# Schem_WS_v2.net
KiCad netlist of a schematic drawn in Altium Designer
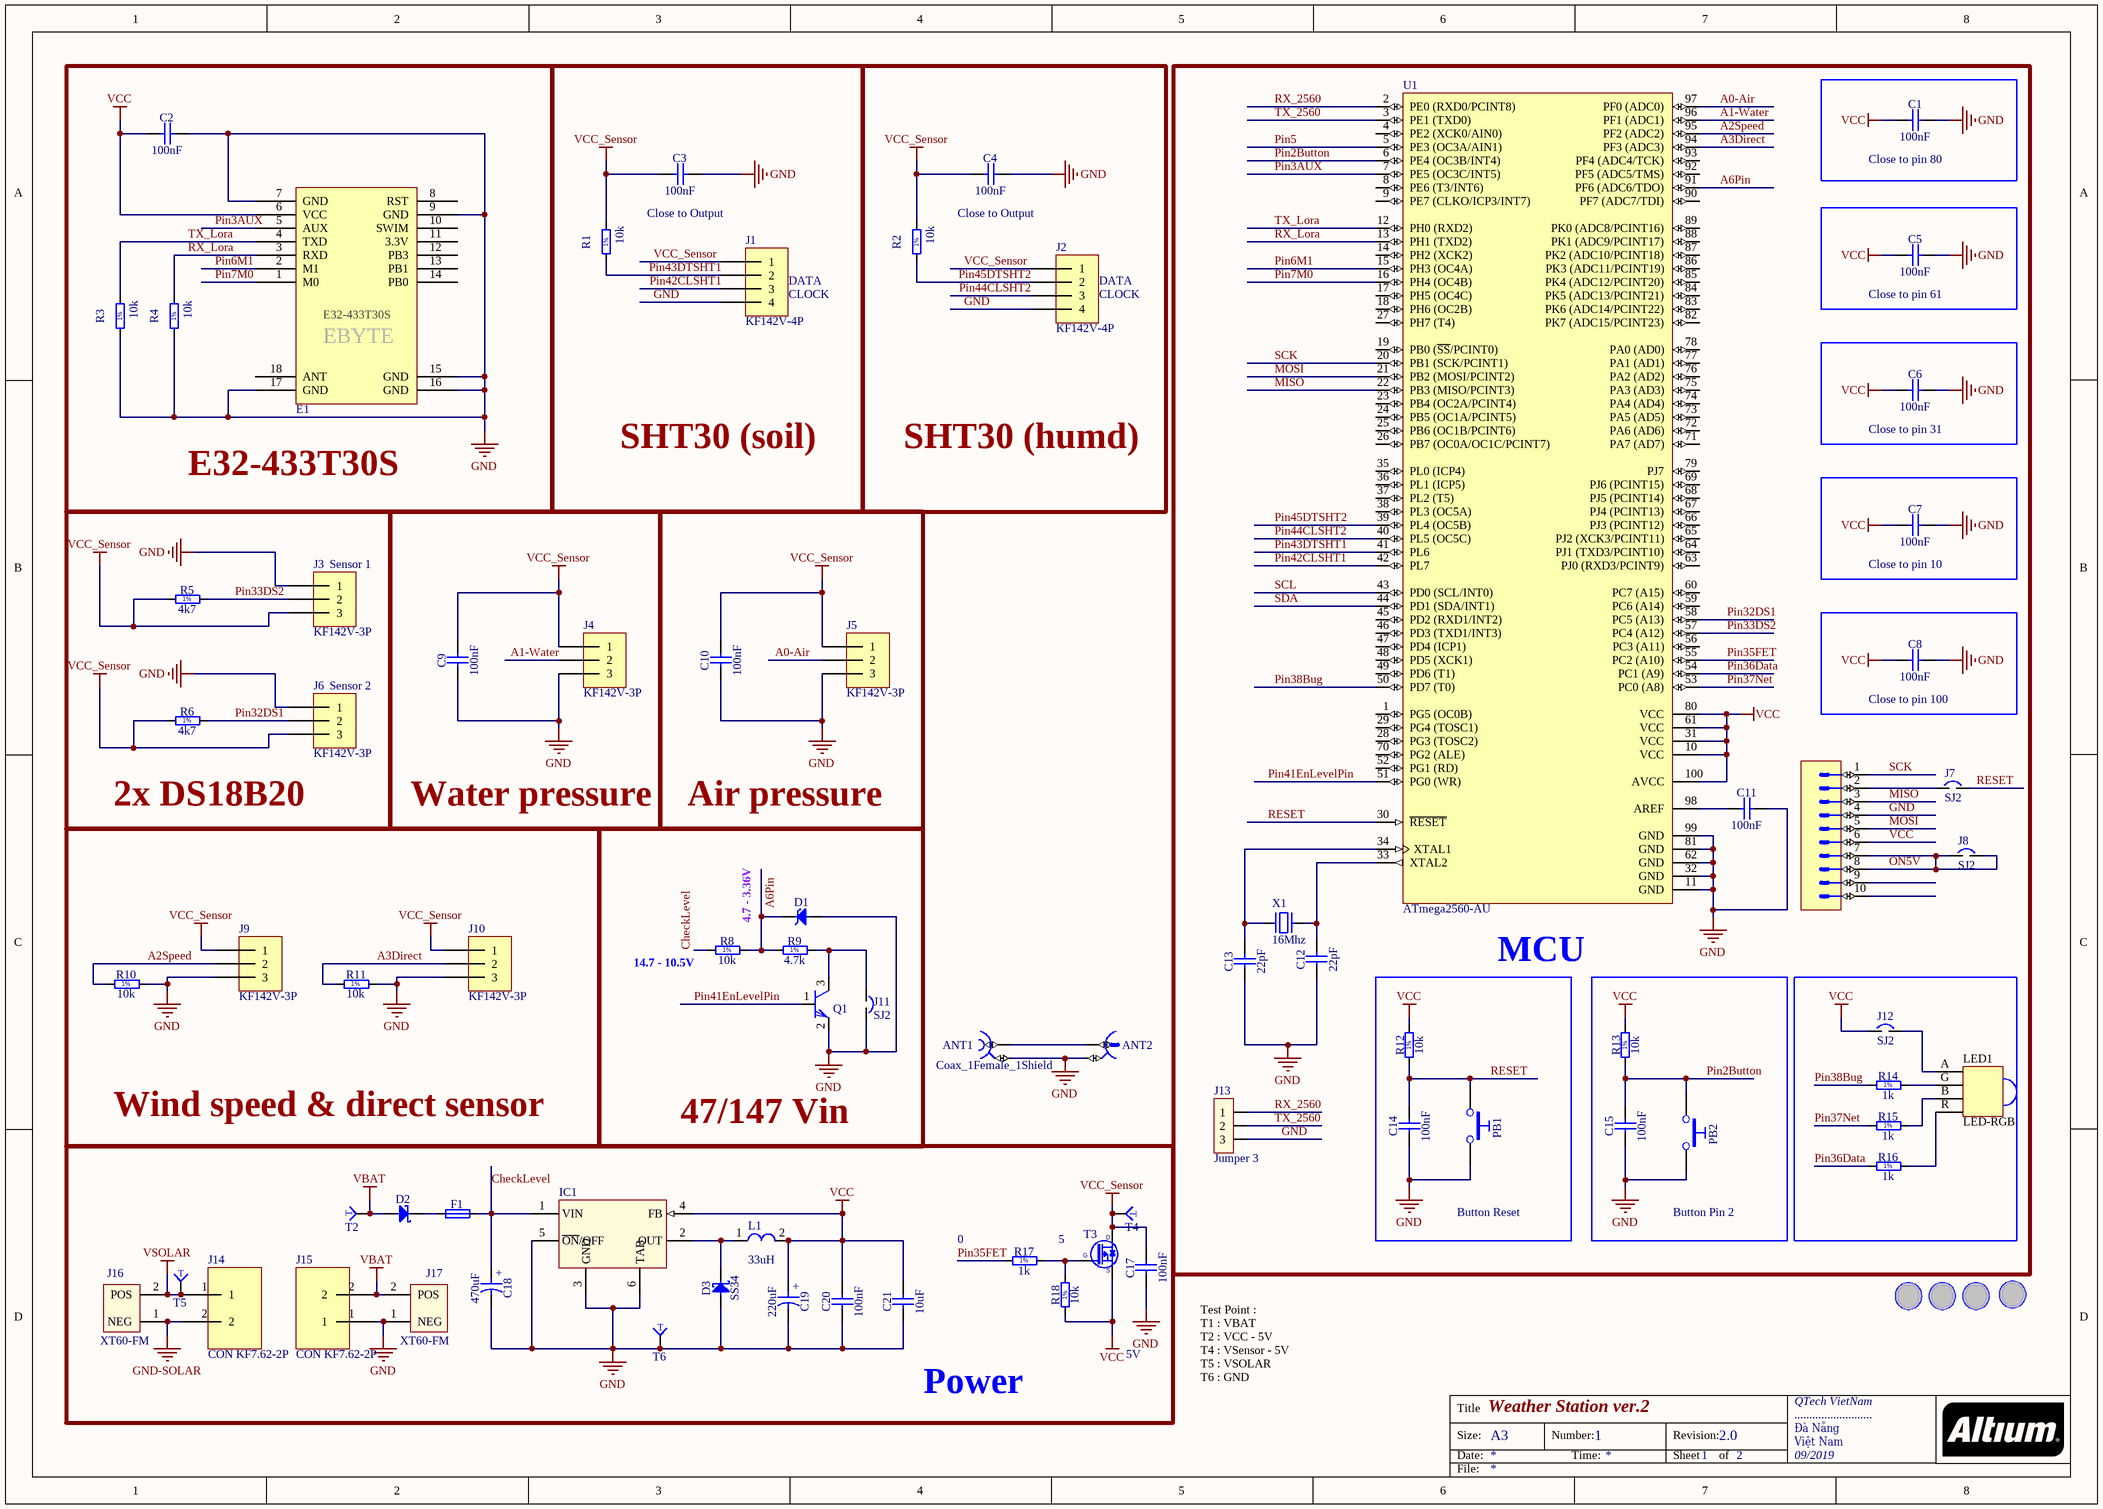
[diagram p0: Schem_WS_v2.SchDoc]

(export (version "E")
  (design (tool "Eeschema 10.0.6"))
  (components
    (comp (ref "ANT1")
      (value "Coax_1Female_1Shield")
      (footprint "HUBER-SUHNER_85 SMA-50-0-101/111 NE")
      (fields
        (field (name "PART NUMBER") "HUBER-SUHNER_85_SMA-50-0-101/111_NE")
        (field (name "MANUFACTURER") "HUBER+SUHNER")
        (field (name "MANUFACTURER PART NUMBER") "85_SMA-50-0-101/111_NE")
        (field (name "AUTHOR") "CERN DEM JLC")
      )
      (libsource (lib "Connectors") (part "Coax_1Female_1Shield"))
    )
    (comp (ref "ANT2")
      (value "U.FL")
      (footprint "HIROSE_U.FL-R-SMT-1(10)")
      (fields
        (field (name "PART NUMBER") "HIROSE_U.FL-R-SMT-1(10)")
        (field (name "MANUFACTURER") "HIROSE (HRS)")
        (field (name "MANUFACTURER PART NUMBER") "U.FL-R-SMT-1(10)")
        (field (name "AUTHOR") "CERN DEM JLC")
      )
      (libsource (lib "Connectors") (part "Coax_1Male_1Shield"))
    )
    (comp (ref "C1")
      (value "100nF")
      (footprint "CAPC1608X87N")
      (description "Non-polarised capacitor")
      (fields
        (field (name "PART NUMBER") "CC0603_100NF_50V_10%_X7R")
        (field (name "VOLTAGE") "50V")
        (field (name "AUTHOR") "CERN DEM JLC")
      )
      (libsource (lib "Capacitors") (part "Capacitor - non polarized"))
    )
    (comp (ref "C2")
      (value "100nF")
      (footprint "CAPC1608X87N")
      (description "Non-polarised capacitor")
      (fields
        (field (name "PART NUMBER") "CC0603_100NF_50V_10%_X7R")
        (field (name "VOLTAGE") "50V")
        (field (name "AUTHOR") "CERN DEM JLC")
      )
      (libsource (lib "Capacitors") (part "Capacitor - non polarized"))
    )
    (comp (ref "C3")
      (value "100nF")
      (footprint "CAPC1608X87N")
      (description "Non-polarised capacitor")
      (fields
        (field (name "PART NUMBER") "CC0603_100NF_50V_10%_X7R")
        (field (name "VOLTAGE") "50V")
        (field (name "AUTHOR") "CERN DEM JLC")
      )
      (libsource (lib "Capacitors") (part "Capacitor - non polarized"))
    )
    (comp (ref "C4")
      (value "100nF")
      (footprint "CAPC1608X87N")
      (description "Non-polarised capacitor")
      (fields
        (field (name "PART NUMBER") "CC0603_100NF_50V_10%_X7R")
        (field (name "VOLTAGE") "50V")
        (field (name "AUTHOR") "CERN DEM JLC")
      )
      (libsource (lib "Capacitors") (part "Capacitor - non polarized"))
    )
    (comp (ref "C5")
      (value "100nF")
      (footprint "CAPC1608X87N")
      (description "Non-polarised capacitor")
      (fields
        (field (name "PART NUMBER") "CC0603_100NF_50V_10%_X7R")
        (field (name "VOLTAGE") "50V")
        (field (name "AUTHOR") "CERN DEM JLC")
      )
      (libsource (lib "Capacitors") (part "Capacitor - non polarized"))
    )
    (comp (ref "C6")
      (value "100nF")
      (footprint "CAPC1608X87N")
      (description "Non-polarised capacitor")
      (fields
        (field (name "PART NUMBER") "CC0603_100NF_50V_10%_X7R")
        (field (name "VOLTAGE") "50V")
        (field (name "AUTHOR") "CERN DEM JLC")
      )
      (libsource (lib "Capacitors") (part "Capacitor - non polarized"))
    )
    (comp (ref "C7")
      (value "100nF")
      (footprint "CAPC1608X87N")
      (description "Non-polarised capacitor")
      (fields
        (field (name "PART NUMBER") "CC0603_100NF_50V_10%_X7R")
        (field (name "VOLTAGE") "50V")
        (field (name "AUTHOR") "CERN DEM JLC")
      )
      (libsource (lib "Capacitors") (part "Capacitor - non polarized"))
    )
    (comp (ref "C8")
      (value "100nF")
      (footprint "CAPC1608X87N")
      (description "Non-polarised capacitor")
      (fields
        (field (name "PART NUMBER") "CC0603_100NF_50V_10%_X7R")
        (field (name "VOLTAGE") "50V")
        (field (name "AUTHOR") "CERN DEM JLC")
      )
      (libsource (lib "Capacitors") (part "Capacitor - non polarized"))
    )
    (comp (ref "C9")
      (value "100nF")
      (footprint "CAPC1608X87N")
      (description "Non-polarised capacitor")
      (fields
        (field (name "PART NUMBER") "CC0603_100NF_50V_10%_X7R")
        (field (name "VOLTAGE") "50V")
        (field (name "AUTHOR") "CERN DEM JLC")
      )
      (libsource (lib "Capacitors") (part "Capacitor - non polarized"))
    )
    (comp (ref "C10")
      (value "100nF")
      (footprint "CAPC1608X87N")
      (description "Non-polarised capacitor")
      (fields
        (field (name "PART NUMBER") "CC0603_100NF_50V_10%_X7R")
        (field (name "VOLTAGE") "50V")
        (field (name "AUTHOR") "CERN DEM JLC")
      )
      (libsource (lib "Capacitors") (part "Capacitor - non polarized"))
    )
    (comp (ref "C11")
      (value "100nF")
      (footprint "CAPC1608X87N")
      (description "Non-polarised capacitor")
      (fields
        (field (name "PART NUMBER") "CC0603_100NF_50V_10%_X7R")
        (field (name "VOLTAGE") "50V")
        (field (name "AUTHOR") "CERN DEM JLC")
      )
      (libsource (lib "Capacitors") (part "Capacitor - non polarized"))
    )
    (comp (ref "C12")
      (value "22pF")
      (footprint "CAPC1608X87N")
      (description "Non-polarised capacitor")
      (fields
        (field (name "PART NUMBER") "CC0603_22PF_50V_5%_NP0")
        (field (name "VOLTAGE") "50V")
        (field (name "AUTHOR") "CERN DEM JLC")
      )
      (libsource (lib "Capacitors") (part "Capacitor - non polarized"))
    )
    (comp (ref "C13")
      (value "22pF")
      (footprint "CAPC1608X87N")
      (description "Non-polarised capacitor")
      (fields
        (field (name "PART NUMBER") "CC0603_22PF_50V_5%_NP0")
        (field (name "VOLTAGE") "50V")
        (field (name "AUTHOR") "CERN DEM JLC")
      )
      (libsource (lib "Capacitors") (part "Capacitor - non polarized"))
    )
    (comp (ref "C14")
      (value "100nF")
      (footprint "CAPC1608X87N")
      (description "Non-polarised capacitor")
      (fields
        (field (name "PART NUMBER") "CC0603_100NF_50V_10%_X7R")
        (field (name "VOLTAGE") "50V")
        (field (name "AUTHOR") "CERN DEM JLC")
      )
      (libsource (lib "Capacitors") (part "Capacitor - non polarized"))
    )
    (comp (ref "C15")
      (value "100nF")
      (footprint "CAPC1608X87N")
      (description "Non-polarised capacitor")
      (fields
        (field (name "PART NUMBER") "CC0603_100NF_50V_10%_X7R")
        (field (name "VOLTAGE") "50V")
        (field (name "AUTHOR") "CERN DEM JLC")
      )
      (libsource (lib "Capacitors") (part "Capacitor - non polarized"))
    )
    (comp (ref "C17")
      (value "100nF")
      (footprint "CAPC1608X87N")
      (description "Non-polarised capacitor")
      (fields
        (field (name "PART NUMBER") "CC0603_100NF_50V_10%_X7R")
        (field (name "VOLTAGE") "50V")
        (field (name "AUTHOR") "CERN DEM JLC")
      )
      (libsource (lib "Capacitors") (part "Capacitor - non polarized"))
    )
    (comp (ref "C18")
      (value "470uF")
      (footprint "CAPAE1030X1020N")
      (description "Polarised capacitor")
      (fields
        (field (name "PART NUMBER") "CAE1030-1020_470UF_25V_20%")
        (field (name "VOLTAGE") "25V")
        (field (name "AUTHOR") "CERN DEM JLC")
      )
      (libsource (lib "Capacitors") (part "Capacitor - polarized"))
    )
    (comp (ref "C19")
      (value "220uF")
      (footprint "CAPMP6032X280N")
      (description "Polarised capacitor")
      (fields
        (field (name "PART NUMBER") "CTE6032-28_100UF_6.3V_10%_LESR0075")
        (field (name "VOLTAGE") "6.3V")
        (field (name "AUTHOR") "CERN DEM JLC")
      )
      (libsource (lib "Capacitors") (part "Capacitor - polarized"))
    )
    (comp (ref "C20")
      (value "100nF")
      (footprint "CAPC1608X87N")
      (description "Non-polarised capacitor")
      (fields
        (field (name "PART NUMBER") "CC0603_100NF_50V_10%_X7R")
        (field (name "VOLTAGE") "50V")
        (field (name "AUTHOR") "CERN DEM JLC")
      )
      (libsource (lib "Capacitors") (part "Capacitor - non polarized"))
    )
    (comp (ref "C21")
      (value "10uF")
      (footprint "CAPC2012X135N")
      (description "Non-polarised capacitor")
      (fields
        (field (name "PART NUMBER") "CC0805_10UF_16V_10%_X5R")
        (field (name "VOLTAGE") "16V")
        (field (name "AUTHOR") "CERN DEM JLC")
      )
      (libsource (lib "Capacitors") (part "Capacitor - non polarized"))
    )
    (comp (ref "D1")
      (value "BZV55-B5V1")
      (footprint "DIOMELF3515N")
      (description "Zener Diode")
      (fields
        (field (name "VOLTAGE") "5V1")
        (field (name "POWER") "500mW")
        (field (name "AUTHOR") "CERN DEM JLC")
      )
      (libsource (lib "ICs And Semiconductors") (part "Diode Zener"))
    )
    (comp (ref "D2")
      (value "SS16")
      (footprint "DIOM5127X229N")
      (description "Schottky Diode")
      (fields
        (field (name "VOLTAGE") "60V")
        (field (name "POWER") "1A")
        (field (name "AUTHOR") "CERN DEM JLC")
      )
      (libsource (lib "ICs And Semiconductors") (part "Diode Schottky"))
    )
    (comp (ref "D3")
      (value "SS34")
      (footprint "DIOM5127X229N")
      (description "Schottky Diode")
      (fields
        (field (name "PART NUMBER") "SS16")
        (field (name "VOLTAGE") "60V")
        (field (name "AUTHOR") "CERN DEM JLC")
      )
      (libsource (lib "ICs And Semiconductors") (part "Diode Schottky"))
    )
    (comp (ref "E1")
      (value "E32-T30S")
      (footprint "E32-433T30S")
      (description "Lora Ebyte E32-T30S Module")
      (libsource (lib "alib_pnphien") (part "E32-433T30S"))
    )
    (comp (ref "F1")
      (value "140mA-60V")
      (footprint "FUSRC4632X90N")
      (description "Fuse")
      (fields
        (field (name "PART NUMBER") "FUSR1812_TYCO-MINISMDC014F")
        (field (name "MANUFACTURER") "TYCO ELECTRONICS")
        (field (name "AUTHOR") "CERN DEM JLC")
      )
      (libsource (lib "Eletro-mechanical") (part "Fuse"))
    )
    (comp (ref "HOLE1")
      (value "HOLE")
      (footprint "HOLE M3")
      (libsource (lib "alib_pnphien") (part "HOLE M3"))
    )
    (comp (ref "HOLE2")
      (value "HOLE")
      (footprint "HOLE M3")
      (libsource (lib "alib_pnphien") (part "HOLE M3"))
    )
    (comp (ref "HOLE3")
      (value "HOLE")
      (footprint "HOLE M3")
      (libsource (lib "alib_pnphien") (part "HOLE M3"))
    )
    (comp (ref "HOLE4")
      (value "HOLE")
      (footprint "HOLE M3")
      (libsource (lib "alib_pnphien") (part "HOLE M3"))
    )
    (comp (ref "IC1")
      (value "LM2596")
      (footprint "TO263-5")
      (libsource (lib "alib_pnphien") (part "LM2596-5V"))
    )
    (comp (ref "J1")
      (value "KF142V-4P")
      (footprint "CON KF142V-4P-5.08")
      (description "CON KF142V-4P-5.08")
      (libsource (lib "alib_pnphien") (part "CON KF142V-4P-5.08"))
    )
    (comp (ref "J2")
      (value "KF142V-4P")
      (footprint "CON KF142V-4P-5.08")
      (description "CON KF142V-4P-5.08")
      (libsource (lib "alib_pnphien") (part "CON KF142V-4P-5.08"))
    )
    (comp (ref "J3")
      (value "KF142V-3P")
      (footprint "CON KF142V-3P-5.08")
      (description "CON KF142V-3P-5.08")
      (libsource (lib "alib_pnphien") (part "CON KF142V-3P-5.08"))
    )
    (comp (ref "J4")
      (value "KF142V-3P")
      (footprint "CON KF142V-3P-5.08")
      (description "CON KF142V-3P-5.08")
      (libsource (lib "alib_pnphien") (part "CON KF142V-3P-5.08"))
    )
    (comp (ref "J5")
      (value "KF142V-3P")
      (footprint "CON KF142V-3P-5.08")
      (description "CON KF142V-3P-5.08")
      (libsource (lib "alib_pnphien") (part "CON KF142V-3P-5.08"))
    )
    (comp (ref "J6")
      (value "KF142V-3P")
      (footprint "CON KF142V-3P-5.08")
      (description "CON KF142V-3P-5.08")
      (libsource (lib "alib_pnphien") (part "CON KF142V-3P-5.08"))
    )
    (comp (ref "J7")
      (value "SJ2")
      (footprint "SJ2")
      (description "Solder Jump2")
      (libsource (lib "sdc") (part "SJ2"))
    )
    (comp (ref "J8")
      (value "SJ2")
      (footprint "SJ2")
      (description "Solder Jump2")
      (libsource (lib "sdc") (part "SJ2"))
    )
    (comp (ref "J9")
      (value "KF142V-3P")
      (footprint "CON KF142V-3P-5.08")
      (description "CON KF142V-3P-5.08")
      (libsource (lib "alib_pnphien") (part "CON KF142V-3P-5.08"))
    )
    (comp (ref "J10")
      (value "KF142V-3P")
      (footprint "CON KF142V-3P-5.08")
      (description "CON KF142V-3P-5.08")
      (libsource (lib "alib_pnphien") (part "CON KF142V-3P-5.08"))
    )
    (comp (ref "J11")
      (value "SJ2")
      (footprint "SJ2")
      (description "Solder Jump2")
      (libsource (lib "sdc") (part "SJ2"))
    )
    (comp (ref "J12")
      (value "SJ2")
      (footprint "SJ2")
      (description "Solder Jump2")
      (libsource (lib "sdc") (part "SJ2"))
    )
    (comp (ref "J13") (value "Jumper 3") (footprint "JP3") (libsource (lib "syhaunguyen") (part "JP3")))
    (comp (ref "J14")
      (value "CON KF7.62-2P")
      (footprint "CON KF7.62-2P")
      (libsource (lib "alib_pnphien") (part "CON KF7.62-2P"))
    )
    (comp (ref "J15")
      (value "CON KF7.62-2P")
      (footprint "CON KF7.62-2P")
      (libsource (lib "") (part "CON KF7.62-2P_1"))
    )
    (comp (ref "J16")
      (value "XT60-FM")
      (footprint "XT60-FM")
      (fields (field (name "MF") "AMASS") (field (name "MP") "XT60-M"))
      (libsource (lib "") (part "XT60-FM_1"))
    )
    (comp (ref "J17")
      (value "XT60-FM")
      (footprint "XT60-FM")
      (fields (field (name "MF") "AMASS") (field (name "MP") "XT60-M"))
      (libsource (lib "alib_pnphien") (part "XT60-FM"))
    )
    (comp (ref "JTAG1")
      (value "Header 10")
      (footprint "3M_N2510-6002RB")
      (description "Connector 10 Male")
      (fields
        (field (name "PART NUMBER") "3M_N2510-6002RB")
        (field (name "MANUFACTURER") "3M")
        (field (name "AUTHOR") "CERN DEM JLC")
      )
      (libsource (lib "Connectors") (part "Connector 10 Male"))
    )
    (comp (ref "L1") (value "33uH") (footprint "L_SMD") (libsource (lib "sdc") (part "L_SMD 33uH")))
    (comp (ref "LED1")
      (value "LED-RGB")
      (footprint "LED-5MMRGBCA")
      (libsource (lib "LIBRARY") (part "LED-RGB"))
    )
    (comp (ref "PB1")
      (value "Push Button")
      (footprint "PB_TYCO_FSMSM")
      (description "Push-Button Switch SPDT")
      (fields
        (field (name "PART NUMBER") "PB_TYCO_FSMSM")
        (field (name "MANUFACTURER") "TYCO ELECTRONICS")
        (field (name "AUTHOR") "CERN DEM JLC")
      )
      (libsource (lib "sdc") (part "PB SPST 1NO-2NO"))
    )
    (comp (ref "PB2")
      (value "Push Button")
      (footprint "PB_TYCO_FSMSM")
      (description "Push-Button Switch SPDT")
      (fields
        (field (name "PART NUMBER") "PB_TYCO_FSMSM")
        (field (name "MANUFACTURER") "TYCO ELECTRONICS")
        (field (name "AUTHOR") "CERN DEM JLC")
      )
      (libsource (lib "sdc") (part "PB SPST 1NO-2NO"))
    )
    (comp (ref "Q1")
      (value "C1815")
      (footprint "SOT23")
      (description "Q2SC1815")
      (fields (field (name "PUBLISHER") "Hoang Nguyen"))
      (libsource (lib "sdc") (part "C1815"))
    )
    (comp (ref "R1")
      (value "10k")
      (footprint "RESC1608X55N")
      (description "Resistor - 1%")
      (fields
        (field (name "PART NUMBER") "R0603_10K_1%_0.1W_100PPM")
        (field (name "POWER") "0.1W")
        (field (name "AUTHOR") "CERN DEM JLC")
      )
      (libsource (lib "Resistors") (part "Resistor - 1%"))
    )
    (comp (ref "R2")
      (value "10k")
      (footprint "RESC1608X55N")
      (description "Resistor - 1%")
      (fields
        (field (name "PART NUMBER") "R0603_10K_1%_0.1W_100PPM")
        (field (name "POWER") "0.1W")
        (field (name "AUTHOR") "CERN DEM JLC")
      )
      (libsource (lib "Resistors") (part "Resistor - 1%"))
    )
    (comp (ref "R3")
      (value "10k")
      (footprint "RESC1608X55N")
      (description "Resistor - 1%")
      (fields
        (field (name "PART NUMBER") "R0603_10K_1%_0.1W_100PPM")
        (field (name "POWER") "0.1W")
        (field (name "AUTHOR") "CERN DEM JLC")
      )
      (libsource (lib "Resistors") (part "Resistor - 1%"))
    )
    (comp (ref "R4")
      (value "10k")
      (footprint "RESC1608X55N")
      (description "Resistor - 1%")
      (fields
        (field (name "PART NUMBER") "R0603_10K_1%_0.1W_100PPM")
        (field (name "POWER") "0.1W")
        (field (name "AUTHOR") "CERN DEM JLC")
      )
      (libsource (lib "Resistors") (part "Resistor - 1%"))
    )
    (comp (ref "R5")
      (value "4k7")
      (footprint "RESC1608X55N")
      (description "Resistor - 1%")
      (fields
        (field (name "PART NUMBER") "R0603_4K7_1%_0.1W_100PPM")
        (field (name "POWER") "0.1W")
        (field (name "AUTHOR") "CERN DEM JLC")
      )
      (libsource (lib "Resistors") (part "Resistor - 1%"))
    )
    (comp (ref "R6")
      (value "4k7")
      (footprint "RESC1608X55N")
      (description "Resistor - 1%")
      (fields
        (field (name "PART NUMBER") "R0603_4K7_1%_0.1W_100PPM")
        (field (name "POWER") "0.1W")
        (field (name "AUTHOR") "CERN DEM JLC")
      )
      (libsource (lib "Resistors") (part "Resistor - 1%"))
    )
    (comp (ref "R8")
      (value "10k")
      (footprint "RESC1608X55N")
      (description "Resistor - 1%")
      (fields
        (field (name "PART NUMBER") "R0603_2M_1%_0.1W_100PPM")
        (field (name "POWER") "0.1W")
        (field (name "AUTHOR") "CERN DEM JLC")
      )
      (libsource (lib "Resistors") (part "Resistor - 1%"))
    )
    (comp (ref "R9")
      (value "4.7k")
      (footprint "RESC1608X55N")
      (description "Resistor - 1%")
      (fields
        (field (name "PART NUMBER") "R0603_1M_1%_0.1W_100PPM")
        (field (name "POWER") "0.1W")
        (field (name "AUTHOR") "CERN DEM JLC")
      )
      (libsource (lib "Resistors") (part "Resistor - 1%"))
    )
    (comp (ref "R10")
      (value "10k")
      (footprint "RESC1608X55N")
      (description "Resistor - 1%")
      (fields
        (field (name "PART NUMBER") "R0603_160R_1%_0.1W_100PPM")
        (field (name "POWER") "0.1W")
        (field (name "AUTHOR") "CERN DEM JLC")
      )
      (libsource (lib "Resistors") (part "Resistor - 1%"))
    )
    (comp (ref "R11")
      (value "10k")
      (footprint "RESC1608X55N")
      (description "Resistor - 1%")
      (fields
        (field (name "PART NUMBER") "R0603_160R_1%_0.1W_100PPM")
        (field (name "POWER") "0.1W")
        (field (name "AUTHOR") "CERN DEM JLC")
      )
      (libsource (lib "Resistors") (part "Resistor - 1%"))
    )
    (comp (ref "R12")
      (value "10k")
      (footprint "RESC1608X55N")
      (description "Resistor - 1%")
      (fields
        (field (name "PART NUMBER") "R0603_10K_1%_0.1W_100PPM")
        (field (name "POWER") "0.1W")
        (field (name "AUTHOR") "CERN DEM JLC")
      )
      (libsource (lib "Resistors") (part "Resistor - 1%"))
    )
    (comp (ref "R13")
      (value "10k")
      (footprint "RESC1608X55N")
      (description "Resistor - 1%")
      (fields
        (field (name "PART NUMBER") "R0603_10K_1%_0.1W_100PPM")
        (field (name "POWER") "0.1W")
        (field (name "AUTHOR") "CERN DEM JLC")
      )
      (libsource (lib "Resistors") (part "Resistor - 1%"))
    )
    (comp (ref "R14")
      (value "1k")
      (footprint "RESC1608X55N")
      (description "Resistor - 1%")
      (fields
        (field (name "PART NUMBER") "R0603_1K_1%_0.1W_100PPM")
        (field (name "POWER") "0.1W")
        (field (name "AUTHOR") "CERN DEM JLC")
      )
      (libsource (lib "Resistors") (part "Resistor - 1%"))
    )
    (comp (ref "R15")
      (value "1k")
      (footprint "RESC1608X55N")
      (description "Resistor - 1%")
      (fields
        (field (name "PART NUMBER") "R0603_1K_1%_0.1W_100PPM")
        (field (name "POWER") "0.1W")
        (field (name "AUTHOR") "CERN DEM JLC")
      )
      (libsource (lib "Resistors") (part "Resistor - 1%"))
    )
    (comp (ref "R16")
      (value "1k")
      (footprint "RESC1608X55N")
      (description "Resistor - 1%")
      (fields
        (field (name "PART NUMBER") "R0603_1K_1%_0.1W_100PPM")
        (field (name "POWER") "0.1W")
        (field (name "AUTHOR") "CERN DEM JLC")
      )
      (libsource (lib "Resistors") (part "Resistor - 1%"))
    )
    (comp (ref "R17")
      (value "1k")
      (footprint "RESC1608X55N")
      (description "Resistor - 1%")
      (fields
        (field (name "PART NUMBER") "R0603_1K_1%_0.1W_100PPM")
        (field (name "POWER") "0.1W")
        (field (name "AUTHOR") "CERN DEM JLC")
      )
      (libsource (lib "Resistors") (part "Resistor - 1%"))
    )
    (comp (ref "R18")
      (value "10k")
      (footprint "RESC1608X55N")
      (description "Resistor - 1%")
      (fields
        (field (name "PART NUMBER") "R0603_10K_1%_0.1W_100PPM")
        (field (name "POWER") "0.1W")
        (field (name "AUTHOR") "CERN DEM JLC")
      )
      (libsource (lib "Resistors") (part "Resistor - 1%"))
    )
    (comp (ref "T2")
      (value "Test Point")
      (footprint "TP1x1r")
      (description "Test Point Round 1x1 mm")
      (libsource (lib "alib_pnphien") (part "TP R1x1"))
    )
    (comp (ref "T3")
      (value "BSH203")
      (footprint "SOT95P230X110-3N")
      (description "P-CHANNEL MOSFET WITH DIODE")
      (fields (field (name "MANUFACTURER") "NXP SEMICONDUCTORS") (field (name "AUTHOR") "CERN DEM JLC"))
      (libsource (lib "ICs And Semiconductors") (part "P-MOSFET-D 1G 2S 3D"))
    )
    (comp (ref "T4")
      (value "Test Point")
      (footprint "TP1x1r")
      (description "Test Point Round 1x1 mm")
      (libsource (lib "alib_pnphien") (part "TP R1x1"))
    )
    (comp (ref "T5")
      (value "Test Point")
      (footprint "TP1x1r")
      (description "Test Point Round 1x1 mm")
      (libsource (lib "alib_pnphien") (part "TP R1x1"))
    )
    (comp (ref "T6")
      (value "Test Point")
      (footprint "TP1x1r")
      (description "Test Point Round 1x1 mm")
      (libsource (lib "alib_pnphien") (part "TP R1x1"))
    )
    (comp (ref "U1")
      (value "ATmega2560-AU")
      (footprint "TQFP100L")
      (libsource (lib "LIBRARY") (part "ATmega2560-AU"))
    )
    (comp (ref "X1")
      (value "16Mhz")
      (footprint "XT2")
      (description "Crystal, 32.768 KHz, -40 to 85 degC, 3.2 x 1.5 x 0.9 mm SMD")
      (libsource (lib "LIBRARY") (part "XT2"))
    )
  )
  (nets
    (net (code "1") (name "/A0-Air") (class "Default")
      (node (ref "J5") (pin "2") (pinfunction "2_2") (pintype "passive"))
      (node (ref "U1") (pin "97") (pinfunction "PF0_(ADC0)_97") (pintype "bidirectional"))
    )
    (net (code "2") (name "/A1-Water") (class "Default")
      (node (ref "J4") (pin "2") (pinfunction "2_2") (pintype "passive"))
      (node (ref "U1") (pin "96") (pinfunction "PF1_(ADC1)_96") (pintype "bidirectional"))
    )
    (net (code "3") (name "/A2Speed") (class "Default")
      (node (ref "J9") (pin "2") (pinfunction "2_2") (pintype "passive"))
      (node (ref "R10") (pin "1") (pinfunction "1_1") (pintype "passive"))
      (node (ref "U1") (pin "95") (pinfunction "PF2_(ADC2)_95") (pintype "bidirectional"))
    )
    (net (code "4") (name "/A3Direct") (class "Default")
      (node (ref "J10") (pin "2") (pinfunction "2_2") (pintype "passive"))
      (node (ref "R11") (pin "1") (pinfunction "1_1") (pintype "passive"))
      (node (ref "U1") (pin "94") (pinfunction "PF3_(ADC3)_94") (pintype "bidirectional"))
    )
    (net (code "5") (name "/A6Pin") (class "Default")
      (node (ref "D1") (pin "1") (pinfunction "C_1") (pintype "passive"))
      (node (ref "R8") (pin "2") (pinfunction "2_2") (pintype "passive"))
      (node (ref "R9") (pin "1") (pinfunction "1_1") (pintype "passive"))
      (node (ref "U1") (pin "91") (pinfunction "PF6_(ADC6/TDO)_91") (pintype "bidirectional"))
    )
    (net (code "6") (name "/CheckLevel") (class "Default")
      (node (ref "C18") (pin "1") (pinfunction "1_1") (pintype "passive"))
      (node (ref "F1") (pin "2") (pinfunction "2_2") (pintype "passive"))
      (node (ref "IC1") (pin "1") (pinfunction "VIN_1") (pintype "passive"))
      (node (ref "R8") (pin "1") (pinfunction "1_1") (pintype "passive"))
    )
    (net (code "7") (name "/MISO") (class "Default")
      (node (ref "JTAG1") (pin "3") (pinfunction "3_3") (pintype "bidirectional"))
      (node (ref "U1") (pin "22") (pinfunction "PB3_(MISO/PCINT3)_22") (pintype "bidirectional"))
    )
    (net (code "8") (name "/MOSI") (class "Default")
      (node (ref "JTAG1") (pin "5") (pinfunction "5_5") (pintype "bidirectional"))
      (node (ref "U1") (pin "21") (pinfunction "PB2_(MOSI/PCINT2)_21") (pintype "bidirectional"))
    )
    (net (code "9") (name "/ON5V") (class "Default")
      (node (ref "J8") (pin "1") (pinfunction "1_1") (pintype "bidirectional"))
      (node (ref "J8") (pin "2") (pinfunction "2_2") (pintype "bidirectional"))
      (node (ref "JTAG1") (pin "7") (pinfunction "7_7") (pintype "bidirectional"))
      (node (ref "JTAG1") (pin "8") (pinfunction "8_8") (pintype "bidirectional"))
    )
    (net (code "10") (name "/Pin2Button") (class "Default")
      (node (ref "C15") (pin "2") (pinfunction "2_2") (pintype "passive"))
      (node (ref "PB2") (pin "1") (pinfunction "1_1") (pintype "passive"))
      (node (ref "R13") (pin "1") (pinfunction "1_1") (pintype "passive"))
      (node (ref "U1") (pin "6") (pinfunction "PE4_(OC3B/INT4)_6") (pintype "bidirectional"))
    )
    (net (code "11") (name "/Pin3AUX") (class "Default")
      (node (ref "E1") (pin "5") (pinfunction "AUX_5") (pintype "passive"))
      (node (ref "U1") (pin "7") (pinfunction "PE5_(OC3C/INT5)_7") (pintype "bidirectional"))
    )
    (net (code "12") (name "/Pin5") (class "Default")
      (node (ref "U1") (pin "5") (pinfunction "PE3_(OC3A/AIN1)_5") (pintype "bidirectional"))
    )
    (net (code "13") (name "/Pin6M1") (class "Default")
      (node (ref "E1") (pin "2") (pinfunction "M1_2") (pintype "passive"))
      (node (ref "U1") (pin "15") (pinfunction "PH3_(OC4A)_15") (pintype "bidirectional"))
    )
    (net (code "14") (name "/Pin7M0") (class "Default")
      (node (ref "E1") (pin "1") (pinfunction "M0_1") (pintype "passive"))
      (node (ref "U1") (pin "16") (pinfunction "PH4_(OC4B)_16") (pintype "bidirectional"))
    )
    (net (code "15") (name "/Pin32DS1") (class "Default")
      (node (ref "J6") (pin "2") (pinfunction "2_2") (pintype "passive"))
      (node (ref "R6") (pin "2") (pinfunction "2_2") (pintype "passive"))
      (node (ref "U1") (pin "58") (pinfunction "PC5_(A13)_58") (pintype "bidirectional"))
    )
    (net (code "16") (name "/Pin33DS2") (class "Default")
      (node (ref "J3") (pin "2") (pinfunction "2_2") (pintype "passive"))
      (node (ref "R5") (pin "2") (pinfunction "2_2") (pintype "passive"))
      (node (ref "U1") (pin "57") (pinfunction "PC4_(A12)_57") (pintype "bidirectional"))
    )
    (net (code "17") (name "/Pin35FET") (class "Default")
      (node (ref "R17") (pin "1") (pinfunction "1_1") (pintype "passive"))
      (node (ref "U1") (pin "55") (pinfunction "PC2_(A10)_55") (pintype "bidirectional"))
    )
    (net (code "18") (name "/Pin36Data") (class "Default")
      (node (ref "R16") (pin "1") (pinfunction "1_1") (pintype "passive"))
      (node (ref "U1") (pin "54") (pinfunction "PC1_(A9)_54") (pintype "bidirectional"))
    )
    (net (code "19") (name "/Pin37Net") (class "Default")
      (node (ref "R15") (pin "1") (pinfunction "1_1") (pintype "passive"))
      (node (ref "U1") (pin "53") (pinfunction "PC0_(A8)_53") (pintype "bidirectional"))
    )
    (net (code "20") (name "/Pin38Bug") (class "Default")
      (node (ref "R14") (pin "1") (pinfunction "1_1") (pintype "passive"))
      (node (ref "U1") (pin "50") (pinfunction "PD7_(T0)_50") (pintype "bidirectional"))
    )
    (net (code "21") (name "/Pin41EnLevelPin") (class "Default")
      (node (ref "Q1") (pin "1") (pinfunction "B_1") (pintype "passive"))
      (node (ref "U1") (pin "51") (pinfunction "PG0_(WR)_51") (pintype "bidirectional"))
    )
    (net (code "22") (name "/Pin42CLSHT1") (class "Default")
      (node (ref "J1") (pin "3") (pinfunction "3_3") (pintype "passive"))
      (node (ref "U1") (pin "42") (pinfunction "PL7_42") (pintype "bidirectional"))
    )
    (net (code "23") (name "/Pin43DTSHT1") (class "Default")
      (node (ref "J1") (pin "2") (pinfunction "2_2") (pintype "passive"))
      (node (ref "R1") (pin "1") (pinfunction "1_1") (pintype "passive"))
      (node (ref "U1") (pin "41") (pinfunction "PL6_41") (pintype "bidirectional"))
    )
    (net (code "24") (name "/Pin44CLSHT2") (class "Default")
      (node (ref "J2") (pin "3") (pinfunction "3_3") (pintype "passive"))
      (node (ref "U1") (pin "40") (pinfunction "PL5_(OC5C)_40") (pintype "bidirectional"))
    )
    (net (code "25") (name "/Pin45DTSHT2") (class "Default")
      (node (ref "J2") (pin "2") (pinfunction "2_2") (pintype "passive"))
      (node (ref "R2") (pin "1") (pinfunction "1_1") (pintype "passive"))
      (node (ref "U1") (pin "39") (pinfunction "PL4_(OC5B)_39") (pintype "bidirectional"))
    )
    (net (code "26") (name "/RESET") (class "Default")
      (node (ref "C14") (pin "2") (pinfunction "2_2") (pintype "passive"))
      (node (ref "J7") (pin "2") (pinfunction "2_2") (pintype "bidirectional"))
      (node (ref "PB1") (pin "1") (pinfunction "1_1") (pintype "passive"))
      (node (ref "R12") (pin "1") (pinfunction "1_1") (pintype "passive"))
      (node (ref "U1") (pin "30") (pinfunction "~{RESET}_30") (pintype "input"))
    )
    (net (code "27") (name "/RX_2560") (class "Default")
      (node (ref "J13") (pin "1") (pinfunction "1_1") (pintype "passive"))
      (node (ref "U1") (pin "2") (pinfunction "PE0_(RXD0/PCINT8)_2") (pintype "bidirectional"))
    )
    (net (code "28") (name "/RX_Lora") (class "Default")
      (node (ref "E1") (pin "3") (pinfunction "RXD_3") (pintype "passive"))
      (node (ref "R4") (pin "2") (pinfunction "2_2") (pintype "passive"))
      (node (ref "U1") (pin "13") (pinfunction "PH1_(TXD2)_13") (pintype "bidirectional"))
    )
    (net (code "29") (name "/SCK") (class "Default")
      (node (ref "JTAG1") (pin "1") (pinfunction "1_1") (pintype "bidirectional"))
      (node (ref "U1") (pin "20") (pinfunction "PB1_(SCK/PCINT1)_20") (pintype "bidirectional"))
    )
    (net (code "30") (name "/SCL") (class "Default")
      (node (ref "U1") (pin "43") (pinfunction "PD0_(SCL/INT0)_43") (pintype "bidirectional"))
    )
    (net (code "31") (name "/SDA") (class "Default")
      (node (ref "U1") (pin "44") (pinfunction "PD1_(SDA/INT1)_44") (pintype "bidirectional"))
    )
    (net (code "32") (name "/TX_2560") (class "Default")
      (node (ref "J13") (pin "2") (pinfunction "2_2") (pintype "passive"))
      (node (ref "U1") (pin "3") (pinfunction "PE1_(TXD0)_3") (pintype "bidirectional"))
    )
    (net (code "33") (name "/TX_Lora") (class "Default")
      (node (ref "E1") (pin "4") (pinfunction "TXD_4") (pintype "passive"))
      (node (ref "R3") (pin "2") (pinfunction "2_2") (pintype "passive"))
      (node (ref "U1") (pin "12") (pinfunction "PH0_(RXD2)_12") (pintype "bidirectional"))
    )
    (net (code "34") (name "GND") (class "Default")
      (node (ref "ANT1") (pin "2") (pinfunction "2_2") (pintype "bidirectional"))
      (node (ref "ANT2") (pin "2") (pinfunction "2_2") (pintype "bidirectional"))
      (node (ref "C1") (pin "2") (pinfunction "2_2") (pintype "passive"))
      (node (ref "C10") (pin "1") (pinfunction "1_1") (pintype "passive"))
      (node (ref "C11") (pin "2") (pinfunction "2_2") (pintype "passive"))
      (node (ref "C12") (pin "1") (pinfunction "1_1") (pintype "passive"))
      (node (ref "C13") (pin "1") (pinfunction "1_1") (pintype "passive"))
      (node (ref "C14") (pin "1") (pinfunction "1_1") (pintype "passive"))
      (node (ref "C15") (pin "1") (pinfunction "1_1") (pintype "passive"))
      (node (ref "C17") (pin "1") (pinfunction "1_1") (pintype "passive"))
      (node (ref "C18") (pin "2") (pinfunction "2_2") (pintype "passive"))
      (node (ref "C19") (pin "2") (pinfunction "2_2") (pintype "passive"))
      (node (ref "C2") (pin "2") (pinfunction "2_2") (pintype "passive"))
      (node (ref "C20") (pin "1") (pinfunction "1_1") (pintype "passive"))
      (node (ref "C21") (pin "1") (pinfunction "1_1") (pintype "passive"))
      (node (ref "C3") (pin "2") (pinfunction "2_2") (pintype "passive"))
      (node (ref "C4") (pin "2") (pinfunction "2_2") (pintype "passive"))
      (node (ref "C5") (pin "2") (pinfunction "2_2") (pintype "passive"))
      (node (ref "C6") (pin "2") (pinfunction "2_2") (pintype "passive"))
      (node (ref "C7") (pin "2") (pinfunction "2_2") (pintype "passive"))
      (node (ref "C8") (pin "2") (pinfunction "2_2") (pintype "passive"))
      (node (ref "C9") (pin "1") (pinfunction "1_1") (pintype "passive"))
      (node (ref "D1") (pin "2") (pinfunction "A_2") (pintype "passive"))
      (node (ref "D3") (pin "2") (pinfunction "A_2") (pintype "passive"))
      (node (ref "E1") (pin "15") (pinfunction "GND_15") (pintype "passive"))
      (node (ref "E1") (pin "16") (pinfunction "GND_16") (pintype "passive"))
      (node (ref "E1") (pin "17") (pinfunction "GND_17") (pintype "passive"))
      (node (ref "E1") (pin "7") (pinfunction "GND_7") (pintype "passive"))
      (node (ref "E1") (pin "9") (pinfunction "GND_9") (pintype "passive"))
      (node (ref "IC1") (pin "3") (pinfunction "GND_3") (pintype "passive"))
      (node (ref "IC1") (pin "5") (pinfunction "~{ON}/OFF_5") (pintype "passive"))
      (node (ref "IC1") (pin "6") (pinfunction "TAB_6") (pintype "passive"))
      (node (ref "J1") (pin "4") (pinfunction "4_4") (pintype "passive"))
      (node (ref "J10") (pin "3") (pinfunction "3_3") (pintype "passive"))
      (node (ref "J11") (pin "2") (pinfunction "2_2") (pintype "bidirectional"))
      (node (ref "J13") (pin "3") (pinfunction "3_3") (pintype "passive"))
      (node (ref "J15") (pin "1") (pinfunction "1_1") (pintype "passive"))
      (node (ref "J17") (pin "1") (pinfunction "NEG_1") (pintype "passive"))
      (node (ref "J2") (pin "4") (pinfunction "4_4") (pintype "passive"))
      (node (ref "J3") (pin "1") (pinfunction "1_1") (pintype "passive"))
      (node (ref "J4") (pin "3") (pinfunction "3_3") (pintype "passive"))
      (node (ref "J5") (pin "3") (pinfunction "3_3") (pintype "passive"))
      (node (ref "J6") (pin "1") (pinfunction "1_1") (pintype "passive"))
      (node (ref "J9") (pin "3") (pinfunction "3_3") (pintype "passive"))
      (node (ref "JTAG1") (pin "4") (pinfunction "4_4") (pintype "bidirectional"))
      (node (ref "PB1") (pin "2") (pinfunction "2_2") (pintype "passive"))
      (node (ref "PB2") (pin "2") (pinfunction "2_2") (pintype "passive"))
      (node (ref "Q1") (pin "2") (pinfunction "E_2") (pintype "passive"))
      (node (ref "R10") (pin "2") (pinfunction "2_2") (pintype "passive"))
      (node (ref "R11") (pin "2") (pinfunction "2_2") (pintype "passive"))
      (node (ref "R3") (pin "1") (pinfunction "1_1") (pintype "passive"))
      (node (ref "R4") (pin "1") (pinfunction "1_1") (pintype "passive"))
      (node (ref "T6") (pin "1") (pinfunction "1_1") (pintype "passive"))
      (node (ref "U1") (pin "11") (pinfunction "GND_11") (pintype "power_in"))
      (node (ref "U1") (pin "32") (pinfunction "GND_32") (pintype "power_in"))
      (node (ref "U1") (pin "62") (pinfunction "GND_62") (pintype "power_in"))
      (node (ref "U1") (pin "81") (pinfunction "GND_81") (pintype "power_in"))
      (node (ref "U1") (pin "99") (pinfunction "GND_99") (pintype "power_in"))
    )
    (net (code "35") (name "GND-SOLAR") (class "Default")
      (node (ref "J14") (pin "2") (pinfunction "2_2") (pintype "passive"))
      (node (ref "J16") (pin "1") (pinfunction "NEG_1") (pintype "passive"))
    )
    (net (code "36") (name "Net-(ANT1-Pad1)") (class "Default")
      (node (ref "ANT1") (pin "1") (pinfunction "1_1") (pintype "bidirectional"))
      (node (ref "ANT2") (pin "1") (pinfunction "1_1") (pintype "bidirectional"))
    )
    (net (code "37") (name "Net-(D2-C)") (class "Default")
      (node (ref "D2") (pin "1") (pinfunction "C_1") (pintype "passive"))
      (node (ref "F1") (pin "1") (pinfunction "1_1") (pintype "passive"))
    )
    (net (code "38") (name "Net-(D3-C)") (class "Default")
      (node (ref "D3") (pin "1") (pinfunction "C_1") (pintype "passive"))
      (node (ref "IC1") (pin "2") (pinfunction "OUT_2") (pintype "passive"))
      (node (ref "L1") (pin "1") (pinfunction "1_1") (pintype "passive"))
    )
    (net (code "39") (name "Net-(J7-Pad1)") (class "Default")
      (node (ref "J7") (pin "1") (pinfunction "1_1") (pintype "bidirectional"))
      (node (ref "JTAG1") (pin "2") (pinfunction "2_2") (pintype "bidirectional"))
    )
    (net (code "40") (name "Net-(J12-Pad2)") (class "Default")
      (node (ref "J12") (pin "2") (pinfunction "2_2") (pintype "bidirectional"))
      (node (ref "LED1") (pin "A") (pinfunction "A_A") (pintype "passive"))
    )
    (net (code "41") (name "Net-(LED1-PadB)") (class "Default")
      (node (ref "LED1") (pin "B") (pinfunction "B_B") (pintype "passive"))
      (node (ref "R15") (pin "2") (pinfunction "2_2") (pintype "passive"))
    )
    (net (code "42") (name "Net-(LED1-PadG)") (class "Default")
      (node (ref "LED1") (pin "G") (pinfunction "G_G") (pintype "passive"))
      (node (ref "R14") (pin "2") (pinfunction "2_2") (pintype "passive"))
    )
    (net (code "43") (name "Net-(LED1-PadR)") (class "Default")
      (node (ref "LED1") (pin "R") (pinfunction "R_R") (pintype "passive"))
      (node (ref "R16") (pin "2") (pinfunction "2_2") (pintype "passive"))
    )
    (net (code "44") (name "Net-(Q1-C)") (class "Default")
      (node (ref "J11") (pin "1") (pinfunction "1_1") (pintype "bidirectional"))
      (node (ref "Q1") (pin "3") (pinfunction "C_3") (pintype "passive"))
      (node (ref "R9") (pin "2") (pinfunction "2_2") (pintype "passive"))
    )
    (net (code "45") (name "Net-(T3-G)") (class "Default")
      (node (ref "R17") (pin "2") (pinfunction "2_2") (pintype "passive"))
      (node (ref "R18") (pin "2") (pinfunction "2_2") (pintype "passive"))
      (node (ref "T3") (pin "1") (pinfunction "G_1") (pintype "passive"))
    )
    (net (code "46") (name "Net-(U1-AREF)") (class "Default")
      (node (ref "C11") (pin "1") (pinfunction "1_1") (pintype "passive"))
      (node (ref "U1") (pin "98") (pinfunction "AREF_98") (pintype "power_in"))
    )
    (net (code "47") (name "Net-(U1-XTAL1)") (class "Default")
      (node (ref "C13") (pin "2") (pinfunction "2_2") (pintype "passive"))
      (node (ref "U1") (pin "34") (pinfunction "XTAL1_34") (pintype "input"))
      (node (ref "X1") (pin "2") (pinfunction "2_2") (pintype "passive"))
    )
    (net (code "48") (name "Net-(U1-XTAL2)") (class "Default")
      (node (ref "C12") (pin "2") (pinfunction "2_2") (pintype "passive"))
      (node (ref "U1") (pin "33") (pinfunction "XTAL2_33") (pintype "output"))
      (node (ref "X1") (pin "1") (pinfunction "1_1") (pintype "passive"))
    )
    (net (code "49") (name "VBAT") (class "Default")
      (node (ref "D2") (pin "2") (pinfunction "A_2") (pintype "passive"))
      (node (ref "J15") (pin "2") (pinfunction "2_2") (pintype "passive"))
      (node (ref "J17") (pin "2") (pinfunction "POS_2") (pintype "passive"))
      (node (ref "T2") (pin "1") (pinfunction "1_1") (pintype "passive"))
    )
    (net (code "50") (name "VCC") (class "Default")
      (node (ref "C1") (pin "1") (pinfunction "1_1") (pintype "passive"))
      (node (ref "C19") (pin "1") (pinfunction "1_1") (pintype "passive"))
      (node (ref "C2") (pin "1") (pinfunction "1_1") (pintype "passive"))
      (node (ref "C20") (pin "2") (pinfunction "2_2") (pintype "passive"))
      (node (ref "C21") (pin "2") (pinfunction "2_2") (pintype "passive"))
      (node (ref "C5") (pin "1") (pinfunction "1_1") (pintype "passive"))
      (node (ref "C6") (pin "1") (pinfunction "1_1") (pintype "passive"))
      (node (ref "C7") (pin "1") (pinfunction "1_1") (pintype "passive"))
      (node (ref "C8") (pin "1") (pinfunction "1_1") (pintype "passive"))
      (node (ref "E1") (pin "6") (pinfunction "VCC_6") (pintype "passive"))
      (node (ref "IC1") (pin "4") (pinfunction "FB_4") (pintype "input"))
      (node (ref "J12") (pin "1") (pinfunction "1_1") (pintype "bidirectional"))
      (node (ref "JTAG1") (pin "6") (pinfunction "6_6") (pintype "bidirectional"))
      (node (ref "L1") (pin "2") (pinfunction "2_2") (pintype "passive"))
      (node (ref "R12") (pin "2") (pinfunction "2_2") (pintype "passive"))
      (node (ref "R13") (pin "2") (pinfunction "2_2") (pintype "passive"))
      (node (ref "R18") (pin "1") (pinfunction "1_1") (pintype "passive"))
      (node (ref "T3") (pin "2") (pinfunction "S_2") (pintype "passive"))
      (node (ref "U1") (pin "10") (pinfunction "VCC_10") (pintype "power_in"))
      (node (ref "U1") (pin "100") (pinfunction "AVCC_100") (pintype "power_in"))
      (node (ref "U1") (pin "31") (pinfunction "VCC_31") (pintype "power_in"))
      (node (ref "U1") (pin "61") (pinfunction "VCC_61") (pintype "power_in"))
      (node (ref "U1") (pin "80") (pinfunction "VCC_80") (pintype "power_in"))
    )
    (net (code "51") (name "VCC_Sensor") (class "Default")
      (node (ref "C10") (pin "2") (pinfunction "2_2") (pintype "passive"))
      (node (ref "C17") (pin "2") (pinfunction "2_2") (pintype "passive"))
      (node (ref "C3") (pin "1") (pinfunction "1_1") (pintype "passive"))
      (node (ref "C4") (pin "1") (pinfunction "1_1") (pintype "passive"))
      (node (ref "C9") (pin "2") (pinfunction "2_2") (pintype "passive"))
      (node (ref "J1") (pin "1") (pinfunction "1_1") (pintype "passive"))
      (node (ref "J10") (pin "1") (pinfunction "1_1") (pintype "passive"))
      (node (ref "J2") (pin "1") (pinfunction "1_1") (pintype "passive"))
      (node (ref "J3") (pin "3") (pinfunction "3_3") (pintype "passive"))
      (node (ref "J4") (pin "1") (pinfunction "1_1") (pintype "passive"))
      (node (ref "J5") (pin "1") (pinfunction "1_1") (pintype "passive"))
      (node (ref "J6") (pin "3") (pinfunction "3_3") (pintype "passive"))
      (node (ref "J9") (pin "1") (pinfunction "1_1") (pintype "passive"))
      (node (ref "R1") (pin "2") (pinfunction "2_2") (pintype "passive"))
      (node (ref "R2") (pin "2") (pinfunction "2_2") (pintype "passive"))
      (node (ref "R5") (pin "1") (pinfunction "1_1") (pintype "passive"))
      (node (ref "R6") (pin "1") (pinfunction "1_1") (pintype "passive"))
      (node (ref "T3") (pin "3") (pinfunction "D_3") (pintype "passive"))
      (node (ref "T4") (pin "1") (pinfunction "1_1") (pintype "passive"))
    )
    (net (code "52") (name "VSOLAR") (class "Default")
      (node (ref "J14") (pin "1") (pinfunction "1_1") (pintype "passive"))
      (node (ref "J16") (pin "2") (pinfunction "POS_2") (pintype "passive"))
      (node (ref "T5") (pin "1") (pinfunction "1_1") (pintype "passive"))
    )
    (net (code "53") (name "unconnected-(E1-3.3V-Pad11)") (class "Default")
      (node (ref "E1") (pin "11") (pinfunction "3.3V_11") (pintype "passive"))
    )
    (net (code "54") (name "unconnected-(E1-ANT-Pad18)") (class "Default")
      (node (ref "E1") (pin "18") (pinfunction "ANT_18") (pintype "passive"))
    )
    (net (code "55") (name "unconnected-(E1-PB0-Pad14)") (class "Default")
      (node (ref "E1") (pin "14") (pinfunction "PB0_14") (pintype "passive"))
    )
    (net (code "56") (name "unconnected-(E1-PB1-Pad13)") (class "Default")
      (node (ref "E1") (pin "13") (pinfunction "PB1_13") (pintype "passive"))
    )
    (net (code "57") (name "unconnected-(E1-PB3-Pad12)") (class "Default")
      (node (ref "E1") (pin "12") (pinfunction "PB3_12") (pintype "passive"))
    )
    (net (code "58") (name "unconnected-(E1-RST-Pad8)") (class "Default")
      (node (ref "E1") (pin "8") (pinfunction "RST_8") (pintype "passive"))
    )
    (net (code "59") (name "unconnected-(E1-SWIM-Pad10)") (class "Default")
      (node (ref "E1") (pin "10") (pinfunction "SWIM_10") (pintype "passive"))
    )
    (net (code "60") (name "unconnected-(JTAG1-Pad9)") (class "Default")
      (node (ref "JTAG1") (pin "9") (pinfunction "9_9") (pintype "bidirectional"))
    )
    (net (code "61") (name "unconnected-(JTAG1-Pad10)") (class "Default")
      (node (ref "JTAG1") (pin "10") (pinfunction "10_10") (pintype "bidirectional"))
    )
    (net (code "62") (name "unconnected-(U1-PA0_(AD0)-Pad78)") (class "Default")
      (node (ref "U1") (pin "78") (pinfunction "PA0_(AD0)_78") (pintype "bidirectional"))
    )
    (net (code "63") (name "unconnected-(U1-PA1_(AD1)-Pad77)") (class "Default")
      (node (ref "U1") (pin "77") (pinfunction "PA1_(AD1)_77") (pintype "bidirectional"))
    )
    (net (code "64") (name "unconnected-(U1-PA2_(AD2)-Pad76)") (class "Default")
      (node (ref "U1") (pin "76") (pinfunction "PA2_(AD2)_76") (pintype "bidirectional"))
    )
    (net (code "65") (name "unconnected-(U1-PA3_(AD3)-Pad75)") (class "Default")
      (node (ref "U1") (pin "75") (pinfunction "PA3_(AD3)_75") (pintype "bidirectional"))
    )
    (net (code "66") (name "unconnected-(U1-PA4_(AD4)-Pad74)") (class "Default")
      (node (ref "U1") (pin "74") (pinfunction "PA4_(AD4)_74") (pintype "bidirectional"))
    )
    (net (code "67") (name "unconnected-(U1-PA5_(AD5)-Pad73)") (class "Default")
      (node (ref "U1") (pin "73") (pinfunction "PA5_(AD5)_73") (pintype "bidirectional"))
    )
    (net (code "68") (name "unconnected-(U1-PA6_(AD6)-Pad72)") (class "Default")
      (node (ref "U1") (pin "72") (pinfunction "PA6_(AD6)_72") (pintype "bidirectional"))
    )
    (net (code "69") (name "unconnected-(U1-PA7_(AD7)-Pad71)") (class "Default")
      (node (ref "U1") (pin "71") (pinfunction "PA7_(AD7)_71") (pintype "bidirectional"))
    )
    (net (code "70") (name "unconnected-(U1-PB0_(~{SS}{slash}PCINT0)-Pad19)") (class "Default")
      (node (ref "U1") (pin "19") (pinfunction "PB0_(~{SS}/PCINT0)_19") (pintype "bidirectional"))
    )
    (net (code "71") (name "unconnected-(U1-PB4_(OC2A{slash}PCINT4)-Pad23)") (class "Default")
      (node (ref "U1") (pin "23") (pinfunction "PB4_(OC2A/PCINT4)_23") (pintype "bidirectional"))
    )
    (net (code "72") (name "unconnected-(U1-PB5_(OC1A{slash}PCINT5)-Pad24)") (class "Default")
      (node (ref "U1") (pin "24") (pinfunction "PB5_(OC1A/PCINT5)_24") (pintype "bidirectional"))
    )
    (net (code "73") (name "unconnected-(U1-PB6_(OC1B{slash}PCINT6)-Pad25)") (class "Default")
      (node (ref "U1") (pin "25") (pinfunction "PB6_(OC1B/PCINT6)_25") (pintype "bidirectional"))
    )
    (net (code "74") (name "unconnected-(U1-PB7_(OC0A{slash}OC1C{slash}PCINT7)-Pad26)") (class "Default")
      (node (ref "U1") (pin "26") (pinfunction "PB7_(OC0A/OC1C/PCINT7)_26") (pintype "bidirectional"))
    )
    (net (code "75") (name "unconnected-(U1-PC3_(A11)-Pad56)") (class "Default")
      (node (ref "U1") (pin "56") (pinfunction "PC3_(A11)_56") (pintype "bidirectional"))
    )
    (net (code "76") (name "unconnected-(U1-PC6_(A14)-Pad59)") (class "Default")
      (node (ref "U1") (pin "59") (pinfunction "PC6_(A14)_59") (pintype "bidirectional"))
    )
    (net (code "77") (name "unconnected-(U1-PC7_(A15)-Pad60)") (class "Default")
      (node (ref "U1") (pin "60") (pinfunction "PC7_(A15)_60") (pintype "bidirectional"))
    )
    (net (code "78") (name "unconnected-(U1-PD2_(RXD1{slash}INT2)-Pad45)") (class "Default")
      (node (ref "U1") (pin "45") (pinfunction "PD2_(RXD1/INT2)_45") (pintype "bidirectional"))
    )
    (net (code "79") (name "unconnected-(U1-PD3_(TXD1{slash}INT3)-Pad46)") (class "Default")
      (node (ref "U1") (pin "46") (pinfunction "PD3_(TXD1/INT3)_46") (pintype "bidirectional"))
    )
    (net (code "80") (name "unconnected-(U1-PD4_(ICP1)-Pad47)") (class "Default")
      (node (ref "U1") (pin "47") (pinfunction "PD4_(ICP1)_47") (pintype "bidirectional"))
    )
    (net (code "81") (name "unconnected-(U1-PD5_(XCK1)-Pad48)") (class "Default")
      (node (ref "U1") (pin "48") (pinfunction "PD5_(XCK1)_48") (pintype "bidirectional"))
    )
    (net (code "82") (name "unconnected-(U1-PD6_(T1)-Pad49)") (class "Default")
      (node (ref "U1") (pin "49") (pinfunction "PD6_(T1)_49") (pintype "bidirectional"))
    )
    (net (code "83") (name "unconnected-(U1-PE2_(XCK0{slash}AIN0)-Pad4)") (class "Default")
      (node (ref "U1") (pin "4") (pinfunction "PE2_(XCK0/AIN0)_4") (pintype "bidirectional"))
    )
    (net (code "84") (name "unconnected-(U1-PE6_(T3{slash}INT6)-Pad8)") (class "Default")
      (node (ref "U1") (pin "8") (pinfunction "PE6_(T3/INT6)_8") (pintype "bidirectional"))
    )
    (net (code "85") (name "unconnected-(U1-PE7_(CLKO{slash}ICP3{slash}INT7)-Pad9)") (class "Default")
      (node (ref "U1") (pin "9") (pinfunction "PE7_(CLKO/ICP3/INT7)_9") (pintype "bidirectional"))
    )
    (net (code "86") (name "unconnected-(U1-PF4_(ADC4{slash}TCK)-Pad93)") (class "Default")
      (node (ref "U1") (pin "93") (pinfunction "PF4_(ADC4/TCK)_93") (pintype "bidirectional"))
    )
    (net (code "87") (name "unconnected-(U1-PF5_(ADC5{slash}TMS)-Pad92)") (class "Default")
      (node (ref "U1") (pin "92") (pinfunction "PF5_(ADC5/TMS)_92") (pintype "bidirectional"))
    )
    (net (code "88") (name "unconnected-(U1-PF7_(ADC7{slash}TDI)-Pad90)") (class "Default")
      (node (ref "U1") (pin "90") (pinfunction "PF7_(ADC7/TDI)_90") (pintype "bidirectional"))
    )
    (net (code "89") (name "unconnected-(U1-PG1_(RD)-Pad52)") (class "Default")
      (node (ref "U1") (pin "52") (pinfunction "PG1_(RD)_52") (pintype "bidirectional"))
    )
    (net (code "90") (name "unconnected-(U1-PG2_(ALE)-Pad70)") (class "Default")
      (node (ref "U1") (pin "70") (pinfunction "PG2_(ALE)_70") (pintype "bidirectional"))
    )
    (net (code "91") (name "unconnected-(U1-PG3_(TOSC2)-Pad28)") (class "Default")
      (node (ref "U1") (pin "28") (pinfunction "PG3_(TOSC2)_28") (pintype "bidirectional"))
    )
    (net (code "92") (name "unconnected-(U1-PG4_(TOSC1)-Pad29)") (class "Default")
      (node (ref "U1") (pin "29") (pinfunction "PG4_(TOSC1)_29") (pintype "bidirectional"))
    )
    (net (code "93") (name "unconnected-(U1-PG5_(OC0B)-Pad1)") (class "Default")
      (node (ref "U1") (pin "1") (pinfunction "PG5_(OC0B)_1") (pintype "bidirectional"))
    )
    (net (code "94") (name "unconnected-(U1-PH2_(XCK2)-Pad14)") (class "Default")
      (node (ref "U1") (pin "14") (pinfunction "PH2_(XCK2)_14") (pintype "bidirectional"))
    )
    (net (code "95") (name "unconnected-(U1-PH5_(OC4C)-Pad17)") (class "Default")
      (node (ref "U1") (pin "17") (pinfunction "PH5_(OC4C)_17") (pintype "bidirectional"))
    )
    (net (code "96") (name "unconnected-(U1-PH6_(OC2B)-Pad18)") (class "Default")
      (node (ref "U1") (pin "18") (pinfunction "PH6_(OC2B)_18") (pintype "bidirectional"))
    )
    (net (code "97") (name "unconnected-(U1-PH7_(T4)-Pad27)") (class "Default")
      (node (ref "U1") (pin "27") (pinfunction "PH7_(T4)_27") (pintype "bidirectional"))
    )
    (net (code "98") (name "unconnected-(U1-PJ0_(RXD3{slash}PCINT9)-Pad63)") (class "Default")
      (node (ref "U1") (pin "63") (pinfunction "PJ0_(RXD3/PCINT9)_63") (pintype "bidirectional"))
    )
    (net (code "99") (name "unconnected-(U1-PJ1_(TXD3{slash}PCINT10)-Pad64)") (class "Default")
      (node (ref "U1") (pin "64") (pinfunction "PJ1_(TXD3/PCINT10)_64") (pintype "bidirectional"))
    )
    (net (code "100") (name "unconnected-(U1-PJ2_(XCK3{slash}PCINT11)-Pad65)") (class "Default")
      (node (ref "U1") (pin "65") (pinfunction "PJ2_(XCK3/PCINT11)_65") (pintype "bidirectional"))
    )
    (net (code "101") (name "unconnected-(U1-PJ3_(PCINT12)-Pad66)") (class "Default")
      (node (ref "U1") (pin "66") (pinfunction "PJ3_(PCINT12)_66") (pintype "bidirectional"))
    )
    (net (code "102") (name "unconnected-(U1-PJ4_(PCINT13)-Pad67)") (class "Default")
      (node (ref "U1") (pin "67") (pinfunction "PJ4_(PCINT13)_67") (pintype "bidirectional"))
    )
    (net (code "103") (name "unconnected-(U1-PJ5_(PCINT14)-Pad68)") (class "Default")
      (node (ref "U1") (pin "68") (pinfunction "PJ5_(PCINT14)_68") (pintype "bidirectional"))
    )
    (net (code "104") (name "unconnected-(U1-PJ6_(PCINT15)-Pad69)") (class "Default")
      (node (ref "U1") (pin "69") (pinfunction "PJ6_(PCINT15)_69") (pintype "bidirectional"))
    )
    (net (code "105") (name "unconnected-(U1-PJ7-Pad79)") (class "Default")
      (node (ref "U1") (pin "79") (pinfunction "PJ7_79") (pintype "bidirectional"))
    )
    (net (code "106") (name "unconnected-(U1-PK0_(ADC8{slash}PCINT16)-Pad89)") (class "Default")
      (node (ref "U1") (pin "89") (pinfunction "PK0_(ADC8/PCINT16)_89") (pintype "bidirectional"))
    )
    (net (code "107") (name "unconnected-(U1-PK1_(ADC9{slash}PCINT17)-Pad88)") (class "Default")
      (node (ref "U1") (pin "88") (pinfunction "PK1_(ADC9/PCINT17)_88") (pintype "bidirectional"))
    )
    (net (code "108") (name "unconnected-(U1-PK2_(ADC10{slash}PCINT18)-Pad87)") (class "Default")
      (node (ref "U1") (pin "87") (pinfunction "PK2_(ADC10/PCINT18)_87") (pintype "bidirectional"))
    )
    (net (code "109") (name "unconnected-(U1-PK3_(ADC11{slash}PCINT19)-Pad86)") (class "Default")
      (node (ref "U1") (pin "86") (pinfunction "PK3_(ADC11/PCINT19)_86") (pintype "bidirectional"))
    )
    (net (code "110") (name "unconnected-(U1-PK4_(ADC12{slash}PCINT20)-Pad85)") (class "Default")
      (node (ref "U1") (pin "85") (pinfunction "PK4_(ADC12/PCINT20)_85") (pintype "bidirectional"))
    )
    (net (code "111") (name "unconnected-(U1-PK5_(ADC13{slash}PCINT21)-Pad84)") (class "Default")
      (node (ref "U1") (pin "84") (pinfunction "PK5_(ADC13/PCINT21)_84") (pintype "bidirectional"))
    )
    (net (code "112") (name "unconnected-(U1-PK6_(ADC14{slash}PCINT22)-Pad83)") (class "Default")
      (node (ref "U1") (pin "83") (pinfunction "PK6_(ADC14/PCINT22)_83") (pintype "bidirectional"))
    )
    (net (code "113") (name "unconnected-(U1-PK7_(ADC15{slash}PCINT23)-Pad82)") (class "Default")
      (node (ref "U1") (pin "82") (pinfunction "PK7_(ADC15/PCINT23)_82") (pintype "bidirectional"))
    )
    (net (code "114") (name "unconnected-(U1-PL0_(ICP4)-Pad35)") (class "Default")
      (node (ref "U1") (pin "35") (pinfunction "PL0_(ICP4)_35") (pintype "bidirectional"))
    )
    (net (code "115") (name "unconnected-(U1-PL1_(ICP5)-Pad36)") (class "Default")
      (node (ref "U1") (pin "36") (pinfunction "PL1_(ICP5)_36") (pintype "bidirectional"))
    )
    (net (code "116") (name "unconnected-(U1-PL2_(T5)-Pad37)") (class "Default")
      (node (ref "U1") (pin "37") (pinfunction "PL2_(T5)_37") (pintype "bidirectional"))
    )
    (net (code "117") (name "unconnected-(U1-PL3_(OC5A)-Pad38)") (class "Default")
      (node (ref "U1") (pin "38") (pinfunction "PL3_(OC5A)_38") (pintype "bidirectional"))
    )
  )
)
